# line_sensor_ver1_1.net
KiCad netlist of a schematic drawn in EAGLE
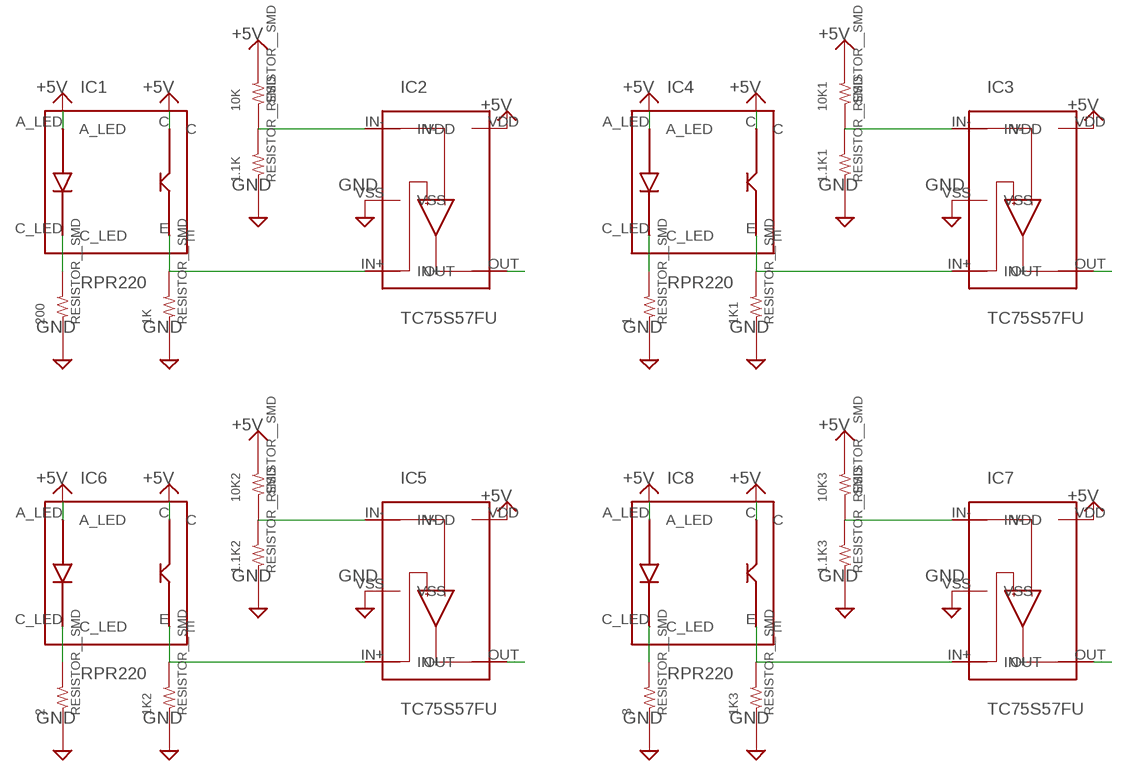
[diagram p0: schematic, sheet 1]

(export (version "E")
  (design (tool "Eeschema 10.0.6"))
  (components
    (comp (ref "1")
      (value "RESISTOR__SMD")
      (footprint "eagle-import:1608")
      (libsource (lib "eagle-import") (part "RESISTOR__SMD"))
    )
    (comp (ref "1.1K")
      (value "RESISTOR__SMD")
      (footprint "eagle-import:1608")
      (libsource (lib "eagle-import") (part "RESISTOR__SMD"))
    )
    (comp (ref "1.1K1")
      (value "RESISTOR__SMD")
      (footprint "eagle-import:1608")
      (libsource (lib "eagle-import") (part "RESISTOR__SMD"))
    )
    (comp (ref "1.1K2")
      (value "RESISTOR__SMD")
      (footprint "eagle-import:1608")
      (libsource (lib "eagle-import") (part "RESISTOR__SMD"))
    )
    (comp (ref "1.1K3")
      (value "RESISTOR__SMD")
      (footprint "eagle-import:1608")
      (libsource (lib "eagle-import") (part "RESISTOR__SMD"))
    )
    (comp (ref "1K")
      (value "RESISTOR__SMD")
      (footprint "eagle-import:1608")
      (libsource (lib "eagle-import") (part "RESISTOR__SMD"))
    )
    (comp (ref "1K1")
      (value "RESISTOR__SMD")
      (footprint "eagle-import:1608")
      (libsource (lib "eagle-import") (part "RESISTOR__SMD"))
    )
    (comp (ref "1K2")
      (value "RESISTOR__SMD")
      (footprint "eagle-import:1608")
      (libsource (lib "eagle-import") (part "RESISTOR__SMD"))
    )
    (comp (ref "1K3")
      (value "RESISTOR__SMD")
      (footprint "eagle-import:1608")
      (libsource (lib "eagle-import") (part "RESISTOR__SMD"))
    )
    (comp (ref "2")
      (value "RESISTOR__SMD")
      (footprint "eagle-import:1608")
      (libsource (lib "eagle-import") (part "RESISTOR__SMD"))
    )
    (comp (ref "3")
      (value "RESISTOR__SMD")
      (footprint "eagle-import:1608")
      (libsource (lib "eagle-import") (part "RESISTOR__SMD"))
    )
    (comp (ref "10K")
      (value "RESISTOR__SMD")
      (footprint "eagle-import:1608")
      (libsource (lib "eagle-import") (part "RESISTOR__SMD"))
    )
    (comp (ref "10K1")
      (value "RESISTOR__SMD")
      (footprint "eagle-import:1608")
      (libsource (lib "eagle-import") (part "RESISTOR__SMD"))
    )
    (comp (ref "10K2")
      (value "RESISTOR__SMD")
      (footprint "eagle-import:1608")
      (libsource (lib "eagle-import") (part "RESISTOR__SMD"))
    )
    (comp (ref "10K3")
      (value "RESISTOR__SMD")
      (footprint "eagle-import:1608")
      (libsource (lib "eagle-import") (part "RESISTOR__SMD"))
    )
    (comp (ref "200")
      (value "RESISTOR__SMD")
      (footprint "eagle-import:1608")
      (libsource (lib "eagle-import") (part "RESISTOR__SMD"))
    )
    (comp (ref "IC1")
      (value "RPR220")
      (footprint "eagle-import:RPR220")
      (libsource (lib "eagle-import") (part "RPR220"))
    )
    (comp (ref "IC2")
      (value "TC75S57FU")
      (footprint "eagle-import:SSOP5-P-0.65A")
      (libsource (lib "eagle-import") (part "TC75S57FU"))
    )
    (comp (ref "IC3")
      (value "TC75S57FU")
      (footprint "eagle-import:SSOP5-P-0.65A")
      (libsource (lib "eagle-import") (part "TC75S57FU"))
    )
    (comp (ref "IC4")
      (value "RPR220")
      (footprint "eagle-import:RPR220")
      (libsource (lib "eagle-import") (part "RPR220"))
    )
    (comp (ref "IC5")
      (value "TC75S57FU")
      (footprint "eagle-import:SSOP5-P-0.65A")
      (libsource (lib "eagle-import") (part "TC75S57FU"))
    )
    (comp (ref "IC6")
      (value "RPR220")
      (footprint "eagle-import:RPR220")
      (libsource (lib "eagle-import") (part "RPR220"))
    )
    (comp (ref "IC7")
      (value "TC75S57FU")
      (footprint "eagle-import:SSOP5-P-0.65A")
      (libsource (lib "eagle-import") (part "TC75S57FU"))
    )
    (comp (ref "IC8")
      (value "RPR220")
      (footprint "eagle-import:RPR220")
      (libsource (lib "eagle-import") (part "RPR220"))
    )
  )
  (nets
    (net (code "1") (name "+5V") (class "Default")
      (node (ref "10K") (pin "2") (pinfunction "P$2_2") (pintype "passive"))
      (node (ref "10K1") (pin "2") (pinfunction "P$2_2") (pintype "passive"))
      (node (ref "10K2") (pin "2") (pinfunction "P$2_2") (pintype "passive"))
      (node (ref "10K3") (pin "2") (pinfunction "P$2_2") (pintype "passive"))
      (node (ref "IC1") (pin "A_LED") (pinfunction "A_LED_A_LED") (pintype "bidirectional"))
      (node (ref "IC1") (pin "C") (pinfunction "C_C") (pintype "bidirectional"))
      (node (ref "IC2") (pin "VDD") (pinfunction "VDD_VDD") (pintype "bidirectional"))
      (node (ref "IC3") (pin "VDD") (pinfunction "VDD_VDD") (pintype "bidirectional"))
      (node (ref "IC4") (pin "A_LED") (pinfunction "A_LED_A_LED") (pintype "bidirectional"))
      (node (ref "IC4") (pin "C") (pinfunction "C_C") (pintype "bidirectional"))
      (node (ref "IC5") (pin "VDD") (pinfunction "VDD_VDD") (pintype "bidirectional"))
      (node (ref "IC6") (pin "A_LED") (pinfunction "A_LED_A_LED") (pintype "bidirectional"))
      (node (ref "IC6") (pin "C") (pinfunction "C_C") (pintype "bidirectional"))
      (node (ref "IC7") (pin "VDD") (pinfunction "VDD_VDD") (pintype "bidirectional"))
      (node (ref "IC8") (pin "A_LED") (pinfunction "A_LED_A_LED") (pintype "bidirectional"))
      (node (ref "IC8") (pin "C") (pinfunction "C_C") (pintype "bidirectional"))
    )
    (net (code "2") (name "GND") (class "Default")
      (node (ref "1") (pin "1") (pinfunction "P$1_1") (pintype "passive"))
      (node (ref "1.1K") (pin "1") (pinfunction "P$1_1") (pintype "passive"))
      (node (ref "1.1K1") (pin "1") (pinfunction "P$1_1") (pintype "passive"))
      (node (ref "1.1K2") (pin "1") (pinfunction "P$1_1") (pintype "passive"))
      (node (ref "1.1K3") (pin "1") (pinfunction "P$1_1") (pintype "passive"))
      (node (ref "1K") (pin "1") (pinfunction "P$1_1") (pintype "passive"))
      (node (ref "1K1") (pin "1") (pinfunction "P$1_1") (pintype "passive"))
      (node (ref "1K2") (pin "1") (pinfunction "P$1_1") (pintype "passive"))
      (node (ref "1K3") (pin "1") (pinfunction "P$1_1") (pintype "passive"))
      (node (ref "2") (pin "1") (pinfunction "P$1_1") (pintype "passive"))
      (node (ref "200") (pin "1") (pinfunction "P$1_1") (pintype "passive"))
      (node (ref "3") (pin "1") (pinfunction "P$1_1") (pintype "passive"))
      (node (ref "IC2") (pin "VSS") (pinfunction "VSS_VSS") (pintype "bidirectional"))
      (node (ref "IC3") (pin "VSS") (pinfunction "VSS_VSS") (pintype "bidirectional"))
      (node (ref "IC5") (pin "VSS") (pinfunction "VSS_VSS") (pintype "bidirectional"))
      (node (ref "IC7") (pin "VSS") (pinfunction "VSS_VSS") (pintype "bidirectional"))
    )
    (net (code "3") (name "Net-(1-P$2)") (class "Default")
      (node (ref "1") (pin "2") (pinfunction "P$2_2") (pintype "passive"))
      (node (ref "IC4") (pin "C_LED") (pinfunction "C_LED_C_LED") (pintype "bidirectional"))
    )
    (net (code "4") (name "Net-(1.1K-P$2)") (class "Default")
      (node (ref "1.1K") (pin "2") (pinfunction "P$2_2") (pintype "passive"))
      (node (ref "10K") (pin "1") (pinfunction "P$1_1") (pintype "passive"))
      (node (ref "IC2") (pin "IN-") (pinfunction "IN-_IN-") (pintype "bidirectional"))
    )
    (net (code "5") (name "Net-(1.1K1-P$2)") (class "Default")
      (node (ref "1.1K1") (pin "2") (pinfunction "P$2_2") (pintype "passive"))
      (node (ref "10K1") (pin "1") (pinfunction "P$1_1") (pintype "passive"))
      (node (ref "IC3") (pin "IN-") (pinfunction "IN-_IN-") (pintype "bidirectional"))
    )
    (net (code "6") (name "Net-(1.1K2-P$2)") (class "Default")
      (node (ref "1.1K2") (pin "2") (pinfunction "P$2_2") (pintype "passive"))
      (node (ref "10K2") (pin "1") (pinfunction "P$1_1") (pintype "passive"))
      (node (ref "IC5") (pin "IN-") (pinfunction "IN-_IN-") (pintype "bidirectional"))
    )
    (net (code "7") (name "Net-(1.1K3-P$2)") (class "Default")
      (node (ref "1.1K3") (pin "2") (pinfunction "P$2_2") (pintype "passive"))
      (node (ref "10K3") (pin "1") (pinfunction "P$1_1") (pintype "passive"))
      (node (ref "IC7") (pin "IN-") (pinfunction "IN-_IN-") (pintype "bidirectional"))
    )
    (net (code "8") (name "Net-(1K-P$2)") (class "Default")
      (node (ref "1K") (pin "2") (pinfunction "P$2_2") (pintype "passive"))
      (node (ref "IC1") (pin "E") (pinfunction "E_E") (pintype "bidirectional"))
      (node (ref "IC2") (pin "IN+") (pinfunction "IN+_IN+") (pintype "bidirectional"))
    )
    (net (code "9") (name "Net-(1K1-P$2)") (class "Default")
      (node (ref "1K1") (pin "2") (pinfunction "P$2_2") (pintype "passive"))
      (node (ref "IC3") (pin "IN+") (pinfunction "IN+_IN+") (pintype "bidirectional"))
      (node (ref "IC4") (pin "E") (pinfunction "E_E") (pintype "bidirectional"))
    )
    (net (code "10") (name "Net-(1K2-P$2)") (class "Default")
      (node (ref "1K2") (pin "2") (pinfunction "P$2_2") (pintype "passive"))
      (node (ref "IC5") (pin "IN+") (pinfunction "IN+_IN+") (pintype "bidirectional"))
      (node (ref "IC6") (pin "E") (pinfunction "E_E") (pintype "bidirectional"))
    )
    (net (code "11") (name "Net-(1K3-P$2)") (class "Default")
      (node (ref "1K3") (pin "2") (pinfunction "P$2_2") (pintype "passive"))
      (node (ref "IC7") (pin "IN+") (pinfunction "IN+_IN+") (pintype "bidirectional"))
      (node (ref "IC8") (pin "E") (pinfunction "E_E") (pintype "bidirectional"))
    )
    (net (code "12") (name "Net-(2-P$2)") (class "Default")
      (node (ref "2") (pin "2") (pinfunction "P$2_2") (pintype "passive"))
      (node (ref "IC6") (pin "C_LED") (pinfunction "C_LED_C_LED") (pintype "bidirectional"))
    )
    (net (code "13") (name "Net-(3-P$2)") (class "Default")
      (node (ref "3") (pin "2") (pinfunction "P$2_2") (pintype "passive"))
      (node (ref "IC8") (pin "C_LED") (pinfunction "C_LED_C_LED") (pintype "bidirectional"))
    )
    (net (code "14") (name "Net-(200-P$2)") (class "Default")
      (node (ref "200") (pin "2") (pinfunction "P$2_2") (pintype "passive"))
      (node (ref "IC1") (pin "C_LED") (pinfunction "C_LED_C_LED") (pintype "bidirectional"))
    )
    (net (code "15") (name "unconnected-(IC2-PadOUT)") (class "Default")
      (node (ref "IC2") (pin "OUT") (pinfunction "OUT_OUT") (pintype "bidirectional"))
    )
    (net (code "16") (name "unconnected-(IC3-PadOUT)") (class "Default")
      (node (ref "IC3") (pin "OUT") (pinfunction "OUT_OUT") (pintype "bidirectional"))
    )
    (net (code "17") (name "unconnected-(IC5-PadOUT)") (class "Default")
      (node (ref "IC5") (pin "OUT") (pinfunction "OUT_OUT") (pintype "bidirectional"))
    )
    (net (code "18") (name "unconnected-(IC7-PadOUT)") (class "Default")
      (node (ref "IC7") (pin "OUT") (pinfunction "OUT_OUT") (pintype "bidirectional"))
    )
  )
)
